# main_board_sch.net
KiCad netlist of a schematic drawn in EAGLE
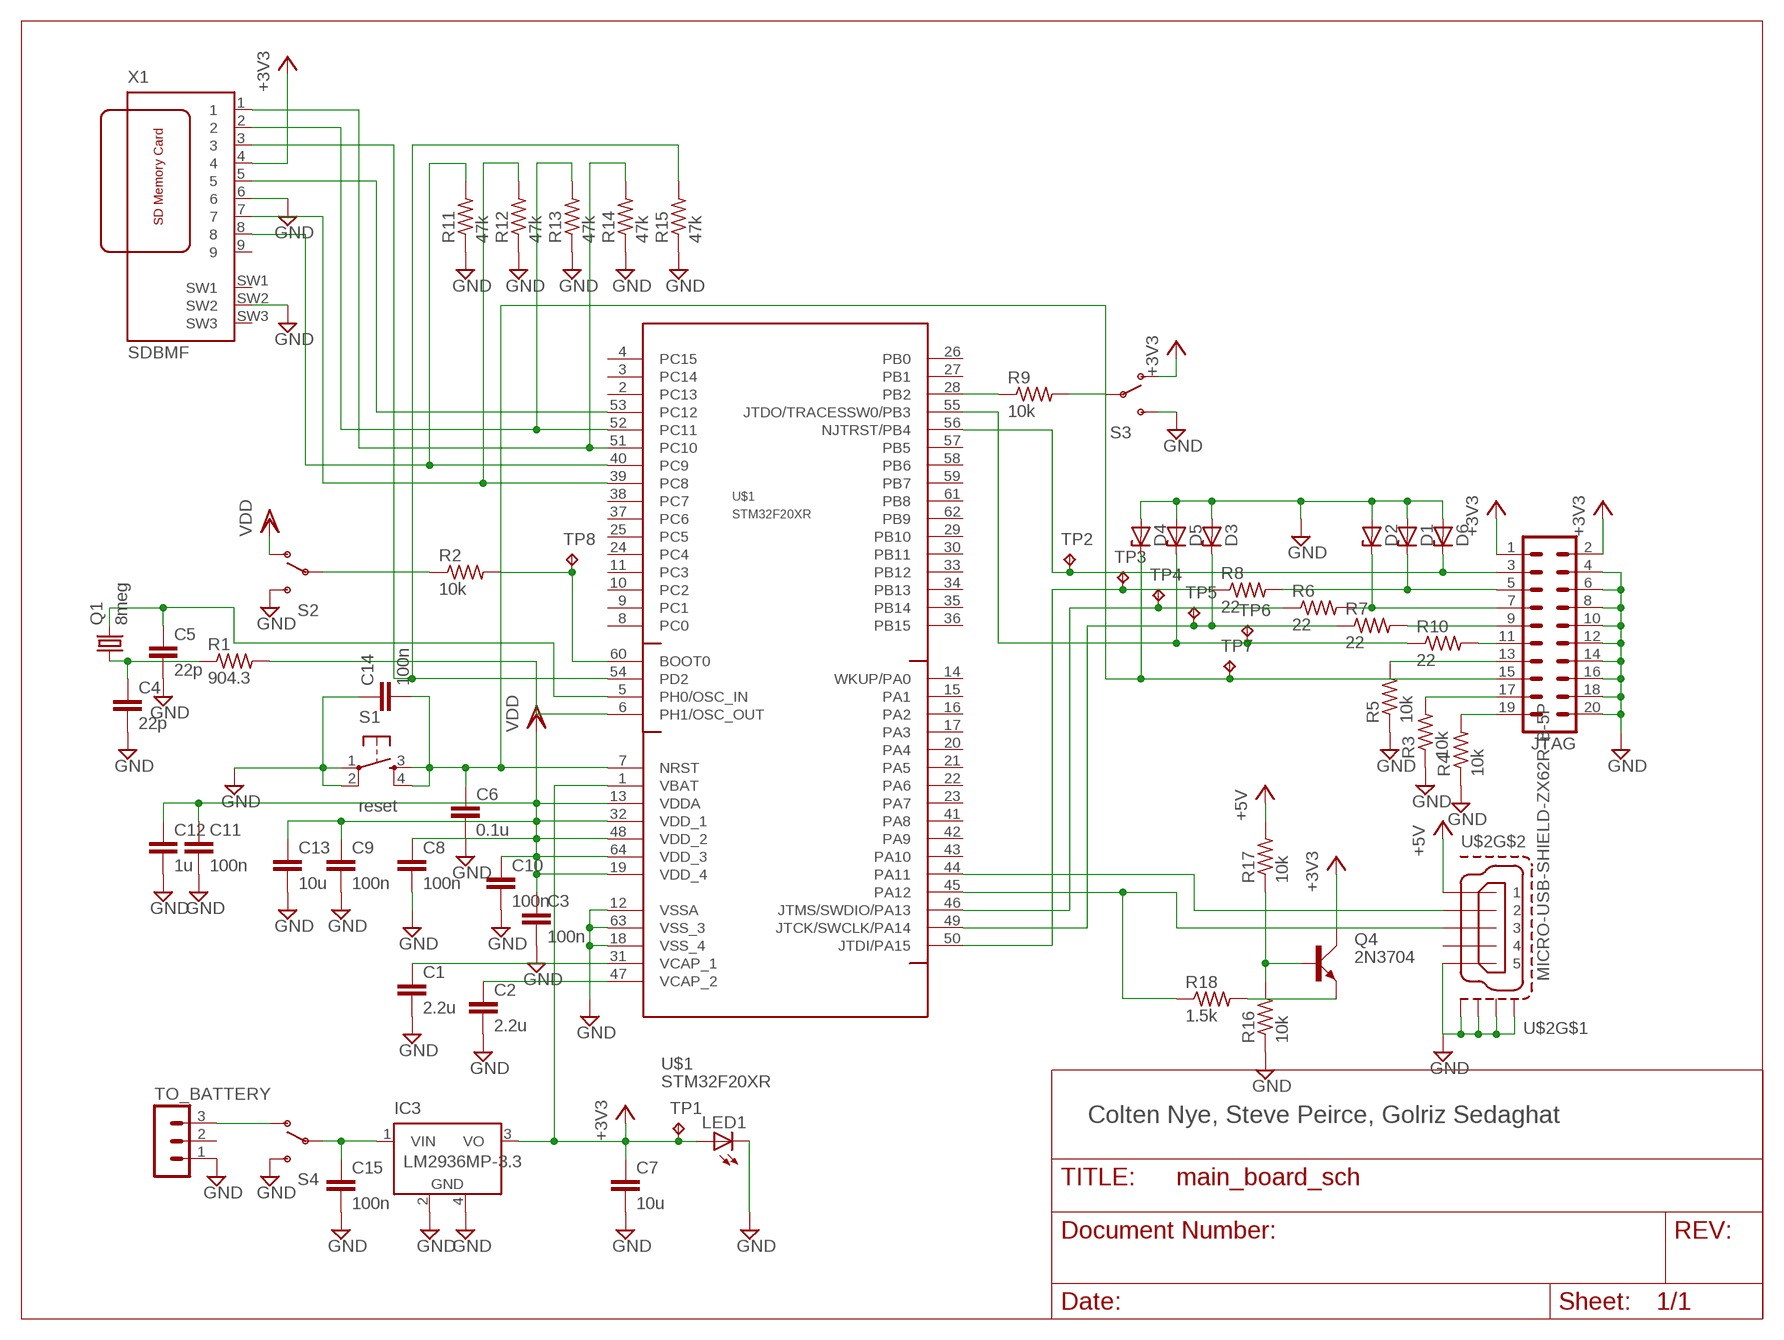
[diagram p0: schematic, sheet 1]

(export (version "E")
  (design (tool "Eeschema 10.0.6"))
  (components
    (comp (ref "C1")
      (value "2.2u")
      (footprint "eagle-import:C0805")
      (libsource (lib "eagle-import") (part "C-EUC0805"))
    )
    (comp (ref "C2")
      (value "2.2u")
      (footprint "eagle-import:C0805")
      (libsource (lib "eagle-import") (part "C-EUC0805"))
    )
    (comp (ref "C3")
      (value "100n")
      (footprint "eagle-import:C0805")
      (libsource (lib "eagle-import") (part "C-EUC0805"))
    )
    (comp (ref "C4")
      (value "22p")
      (footprint "eagle-import:C0805")
      (libsource (lib "eagle-import") (part "C-EUC0805"))
    )
    (comp (ref "C5")
      (value "22p")
      (footprint "eagle-import:C0805")
      (libsource (lib "eagle-import") (part "C-EUC0805"))
    )
    (comp (ref "C6")
      (value "0.1u")
      (footprint "eagle-import:C0805")
      (libsource (lib "eagle-import") (part "C-EUC0805"))
    )
    (comp (ref "C7")
      (value "10u")
      (footprint "eagle-import:C0805")
      (libsource (lib "eagle-import") (part "C-EUC0805"))
    )
    (comp (ref "C8")
      (value "100n")
      (footprint "eagle-import:C0805")
      (libsource (lib "eagle-import") (part "C-EUC0805"))
    )
    (comp (ref "C9")
      (value "100n")
      (footprint "eagle-import:C0805")
      (libsource (lib "eagle-import") (part "C-EUC0805"))
    )
    (comp (ref "C10")
      (value "100n")
      (footprint "eagle-import:C0805")
      (libsource (lib "eagle-import") (part "C-EUC0805"))
    )
    (comp (ref "C11")
      (value "100n")
      (footprint "eagle-import:C0805")
      (libsource (lib "eagle-import") (part "C-EUC0805"))
    )
    (comp (ref "C12")
      (value "1u")
      (footprint "eagle-import:C0805")
      (libsource (lib "eagle-import") (part "C-EUC0805"))
    )
    (comp (ref "C13")
      (value "10u")
      (footprint "eagle-import:C0805")
      (libsource (lib "eagle-import") (part "C-EUC0805"))
    )
    (comp (ref "C14")
      (value "100n")
      (footprint "eagle-import:C0805")
      (libsource (lib "eagle-import") (part "C-EUC0805"))
    )
    (comp (ref "C15")
      (value "100n")
      (footprint "eagle-import:C0805")
      (libsource (lib "eagle-import") (part "C-EUC0805"))
    )
    (comp (ref "D1")
      (value "ZENER-DIODEZD-5")
      (footprint "eagle-import:ZDIO-5")
      (libsource (lib "eagle-import") (part "ZENER-DIODEZD-5"))
    )
    (comp (ref "D2")
      (value "ZENER-DIODEZD-5")
      (footprint "eagle-import:ZDIO-5")
      (libsource (lib "eagle-import") (part "ZENER-DIODEZD-5"))
    )
    (comp (ref "D3")
      (value "ZENER-DIODEZD-5")
      (footprint "eagle-import:ZDIO-5")
      (libsource (lib "eagle-import") (part "ZENER-DIODEZD-5"))
    )
    (comp (ref "D4")
      (value "ZENER-DIODEZD-5")
      (footprint "eagle-import:ZDIO-5")
      (libsource (lib "eagle-import") (part "ZENER-DIODEZD-5"))
    )
    (comp (ref "D5")
      (value "ZENER-DIODEZD-5")
      (footprint "eagle-import:ZDIO-5")
      (libsource (lib "eagle-import") (part "ZENER-DIODEZD-5"))
    )
    (comp (ref "D6")
      (value "ZENER-DIODEZD-5")
      (footprint "eagle-import:ZDIO-5")
      (libsource (lib "eagle-import") (part "ZENER-DIODEZD-5"))
    )
    (comp (ref "IC3")
      (value "LM2936MP-3.3")
      (footprint "eagle-import:SOT223")
      (fields (field (name "MF") "NATIONAL SEMICONDUCTOR") (field (name "MPN") "LM2936MP-3.3/NOPB"))
      (libsource (lib "eagle-import") (part "LM2936MP?-3.3"))
    )
    (comp (ref "JTAG")
      (value "MA10-2")
      (footprint "eagle-import:MA10-2")
      (libsource (lib "eagle-import") (part "MA10-2"))
    )
    (comp (ref "LED1")
      (value "LEDSML0805")
      (footprint "eagle-import:SML0805")
      (libsource (lib "eagle-import") (part "LEDSML0805"))
    )
    (comp (ref "Q1")
      (value "8meg")
      (footprint "eagle-import:HC49_S")
      (libsource (lib "eagle-import") (part "CRYSTALHC49S"))
    )
    (comp (ref "Q4")
      (value "2N3704")
      (footprint "eagle-import:TO92C")
      (libsource (lib "eagle-import") (part "2N3704"))
    )
    (comp (ref "R1")
      (value "904.3")
      (footprint "eagle-import:R0805")
      (libsource (lib "eagle-import") (part "R-US_R0805"))
    )
    (comp (ref "R2")
      (value "10k")
      (footprint "eagle-import:R0805")
      (libsource (lib "eagle-import") (part "R-US_R0805"))
    )
    (comp (ref "R3")
      (value "10k")
      (footprint "eagle-import:R0805")
      (libsource (lib "eagle-import") (part "R-US_R0805"))
    )
    (comp (ref "R4")
      (value "10k")
      (footprint "eagle-import:R0805")
      (libsource (lib "eagle-import") (part "R-US_R0805"))
    )
    (comp (ref "R5")
      (value "10k")
      (footprint "eagle-import:R0805")
      (libsource (lib "eagle-import") (part "R-US_R0805"))
    )
    (comp (ref "R6")
      (value "22")
      (footprint "eagle-import:R0805")
      (libsource (lib "eagle-import") (part "R-US_R0805"))
    )
    (comp (ref "R7")
      (value "22")
      (footprint "eagle-import:R0805")
      (libsource (lib "eagle-import") (part "R-US_R0805"))
    )
    (comp (ref "R8")
      (value "22")
      (footprint "eagle-import:R0805")
      (libsource (lib "eagle-import") (part "R-US_R0805"))
    )
    (comp (ref "R9")
      (value "10k")
      (footprint "eagle-import:R0805")
      (libsource (lib "eagle-import") (part "R-US_R0805"))
    )
    (comp (ref "R10")
      (value "22")
      (footprint "eagle-import:R0805")
      (libsource (lib "eagle-import") (part "R-US_R0805"))
    )
    (comp (ref "R11")
      (value "47k")
      (footprint "eagle-import:R0805")
      (libsource (lib "eagle-import") (part "R-US_R0805"))
    )
    (comp (ref "R12")
      (value "47k")
      (footprint "eagle-import:R0805")
      (libsource (lib "eagle-import") (part "R-US_R0805"))
    )
    (comp (ref "R13")
      (value "47k")
      (footprint "eagle-import:R0805")
      (libsource (lib "eagle-import") (part "R-US_R0805"))
    )
    (comp (ref "R14")
      (value "47k")
      (footprint "eagle-import:R0805")
      (libsource (lib "eagle-import") (part "R-US_R0805"))
    )
    (comp (ref "R15")
      (value "47k")
      (footprint "eagle-import:R0805")
      (libsource (lib "eagle-import") (part "R-US_R0805"))
    )
    (comp (ref "R16")
      (value "10k")
      (footprint "eagle-import:R0805")
      (libsource (lib "eagle-import") (part "R-US_R0805"))
    )
    (comp (ref "R17")
      (value "10k")
      (footprint "eagle-import:R0805")
      (libsource (lib "eagle-import") (part "R-US_R0805"))
    )
    (comp (ref "R18")
      (value "1.5k")
      (footprint "eagle-import:R0805")
      (libsource (lib "eagle-import") (part "R-US_R0805"))
    )
    (comp (ref "S1")
      (value "reset")
      (footprint "eagle-import:TACTILE-SWITCH-SMD")
      (libsource (lib "eagle-import") (part "TAC_SWITCHSMD"))
    )
    (comp (ref "S2")
      (value "SWITCH-SPDT-SMD-A")
      (footprint "eagle-import:SWITCH-SPST-SMD-A")
      (libsource (lib "eagle-import") (part "SWITCH-SPDT-SMD-A"))
    )
    (comp (ref "S3")
      (value "SWITCH-SPDT-SMD-A")
      (footprint "eagle-import:SWITCH-SPST-SMD-A")
      (libsource (lib "eagle-import") (part "SWITCH-SPDT-SMD-A"))
    )
    (comp (ref "S4")
      (value "SWITCH-SPDT-SMD-A")
      (footprint "eagle-import:SWITCH-SPST-SMD-A")
      (libsource (lib "eagle-import") (part "SWITCH-SPDT-SMD-A"))
    )
    (comp (ref "TO_BATTERY")
      (value "MA03-1")
      (footprint "eagle-import:MA03-1")
      (libsource (lib "eagle-import") (part "MA03-1"))
    )
    (comp (ref "TP1")
      (value "TPB1,27")
      (footprint "eagle-import:B1,27")
      (libsource (lib "eagle-import") (part "TPB1,27"))
    )
    (comp (ref "TP2")
      (value "TPB1,27")
      (footprint "eagle-import:B1,27")
      (libsource (lib "eagle-import") (part "TPB1,27"))
    )
    (comp (ref "TP3")
      (value "TPB1,27")
      (footprint "eagle-import:B1,27")
      (libsource (lib "eagle-import") (part "TPB1,27"))
    )
    (comp (ref "TP4")
      (value "TPB1,27")
      (footprint "eagle-import:B1,27")
      (libsource (lib "eagle-import") (part "TPB1,27"))
    )
    (comp (ref "TP5")
      (value "TPB1,27")
      (footprint "eagle-import:B1,27")
      (libsource (lib "eagle-import") (part "TPB1,27"))
    )
    (comp (ref "TP6")
      (value "TPB1,27")
      (footprint "eagle-import:B1,27")
      (libsource (lib "eagle-import") (part "TPB1,27"))
    )
    (comp (ref "TP7")
      (value "TPB1,27")
      (footprint "eagle-import:B1,27")
      (libsource (lib "eagle-import") (part "TPB1,27"))
    )
    (comp (ref "TP8")
      (value "TPB1,27")
      (footprint "eagle-import:B1,27")
      (libsource (lib "eagle-import") (part "TPB1,27"))
    )
    (comp (ref "U$1")
      (value "STM32F20XR")
      (footprint "eagle-import:LQFP64")
      (libsource (lib "eagle-import") (part "STM32F20XR"))
    )
    (comp (ref "U$2")
      (value "MICRO-USB-SHIELD-ZX62R-B-5P")
      (footprint "eagle-import:ZX62R-B-5P")
      (libsource (lib "eagle-import") (part "MICRO-USB-SHIELD-ZX62R-B-5P"))
    )
    (comp (ref "X1")
      (value "SDBMF")
      (footprint "eagle-import:SDBMF-009XXBXX2")
      (libsource (lib "eagle-import") (part "SDBMF"))
    )
  )
  (nets
    (net (code "1") (name "+3V3") (class "Default")
      (node (ref "C7") (pin "1") (pinfunction "1_1") (pintype "passive"))
      (node (ref "IC3") (pin "3") (pinfunction "VO_3") (pintype "passive"))
      (node (ref "JTAG") (pin "1") (pinfunction "1_1") (pintype "passive"))
      (node (ref "JTAG") (pin "2") (pinfunction "2_2") (pintype "passive"))
      (node (ref "LED1") (pin "A") (pinfunction "A_A") (pintype "passive"))
      (node (ref "Q4") (pin "C") (pinfunction "C_C") (pintype "passive"))
      (node (ref "S3") (pin "1") (pinfunction "O_1") (pintype "passive"))
      (node (ref "TP1") (pin "TP") (pinfunction "TP_TP") (pintype "input"))
      (node (ref "U$1") (pin "1") (pinfunction "VBAT_1") (pintype "power_in"))
      (node (ref "X1") (pin "4") (pinfunction "4_4") (pintype "passive"))
    )
    (net (code "2") (name "+5V") (class "Default")
      (node (ref "R17") (pin "2") (pinfunction "2_2") (pintype "passive"))
      (node (ref "U$2") (pin "1") (pinfunction "1_1") (pintype "input"))
    )
    (net (code "3") (name "GND") (class "Default")
      (node (ref "C1") (pin "2") (pinfunction "2_2") (pintype "passive"))
      (node (ref "C10") (pin "2") (pinfunction "2_2") (pintype "passive"))
      (node (ref "C11") (pin "2") (pinfunction "2_2") (pintype "passive"))
      (node (ref "C12") (pin "2") (pinfunction "2_2") (pintype "passive"))
      (node (ref "C13") (pin "2") (pinfunction "2_2") (pintype "passive"))
      (node (ref "C14") (pin "1") (pinfunction "1_1") (pintype "passive"))
      (node (ref "C15") (pin "2") (pinfunction "2_2") (pintype "passive"))
      (node (ref "C2") (pin "2") (pinfunction "2_2") (pintype "passive"))
      (node (ref "C3") (pin "2") (pinfunction "2_2") (pintype "passive"))
      (node (ref "C4") (pin "2") (pinfunction "2_2") (pintype "passive"))
      (node (ref "C5") (pin "2") (pinfunction "2_2") (pintype "passive"))
      (node (ref "C6") (pin "2") (pinfunction "2_2") (pintype "passive"))
      (node (ref "C7") (pin "2") (pinfunction "2_2") (pintype "passive"))
      (node (ref "C8") (pin "2") (pinfunction "2_2") (pintype "passive"))
      (node (ref "C9") (pin "2") (pinfunction "2_2") (pintype "passive"))
      (node (ref "D1") (pin "A") (pinfunction "A_A") (pintype "passive"))
      (node (ref "D2") (pin "A") (pinfunction "A_A") (pintype "passive"))
      (node (ref "D3") (pin "A") (pinfunction "A_A") (pintype "passive"))
      (node (ref "D4") (pin "A") (pinfunction "A_A") (pintype "passive"))
      (node (ref "D5") (pin "A") (pinfunction "A_A") (pintype "passive"))
      (node (ref "D6") (pin "A") (pinfunction "A_A") (pintype "passive"))
      (node (ref "IC3") (pin "2") (pinfunction "GND_2") (pintype "passive"))
      (node (ref "IC3") (pin "4") (pinfunction "GND_4") (pintype "passive"))
      (node (ref "JTAG") (pin "10") (pinfunction "10_10") (pintype "passive"))
      (node (ref "JTAG") (pin "12") (pinfunction "12_12") (pintype "passive"))
      (node (ref "JTAG") (pin "14") (pinfunction "14_14") (pintype "passive"))
      (node (ref "JTAG") (pin "16") (pinfunction "16_16") (pintype "passive"))
      (node (ref "JTAG") (pin "18") (pinfunction "18_18") (pintype "passive"))
      (node (ref "JTAG") (pin "20") (pinfunction "20_20") (pintype "passive"))
      (node (ref "JTAG") (pin "4") (pinfunction "4_4") (pintype "passive"))
      (node (ref "JTAG") (pin "6") (pinfunction "6_6") (pintype "passive"))
      (node (ref "JTAG") (pin "8") (pinfunction "8_8") (pintype "passive"))
      (node (ref "LED1") (pin "C") (pinfunction "C_C") (pintype "passive"))
      (node (ref "R11") (pin "1") (pinfunction "1_1") (pintype "passive"))
      (node (ref "R12") (pin "1") (pinfunction "1_1") (pintype "passive"))
      (node (ref "R13") (pin "1") (pinfunction "1_1") (pintype "passive"))
      (node (ref "R14") (pin "1") (pinfunction "1_1") (pintype "passive"))
      (node (ref "R15") (pin "1") (pinfunction "1_1") (pintype "passive"))
      (node (ref "R16") (pin "1") (pinfunction "1_1") (pintype "passive"))
      (node (ref "R3") (pin "1") (pinfunction "1_1") (pintype "passive"))
      (node (ref "R4") (pin "1") (pinfunction "1_1") (pintype "passive"))
      (node (ref "R5") (pin "1") (pinfunction "1_1") (pintype "passive"))
      (node (ref "S1") (pin "1") (pinfunction "1_1") (pintype "passive"))
      (node (ref "S1") (pin "2") (pinfunction "2_2") (pintype "passive"))
      (node (ref "S2") (pin "3") (pinfunction "S_3") (pintype "passive"))
      (node (ref "S3") (pin "3") (pinfunction "S_3") (pintype "passive"))
      (node (ref "S4") (pin "3") (pinfunction "S_3") (pintype "passive"))
      (node (ref "TO_BATTERY") (pin "1") (pinfunction "1_1") (pintype "passive"))
      (node (ref "U$1") (pin "12") (pinfunction "VSSA_12") (pintype "power_in"))
      (node (ref "U$1") (pin "18") (pinfunction "VSS_4_18") (pintype "power_in"))
      (node (ref "U$1") (pin "63") (pinfunction "VSS_3_63") (pintype "power_in"))
      (node (ref "U$2") (pin "5") (pinfunction "5_5") (pintype "input"))
      (node (ref "U$2") (pin "M1") (pinfunction "S1_M1") (pintype "passive"))
      (node (ref "U$2") (pin "M2") (pinfunction "S2_M2") (pintype "passive"))
      (node (ref "U$2") (pin "M3") (pinfunction "S3_M3") (pintype "passive"))
      (node (ref "U$2") (pin "M4") (pinfunction "S4_M4") (pintype "passive"))
      (node (ref "X1") (pin "6") (pinfunction "6_6") (pintype "passive"))
      (node (ref "X1") (pin "SW2") (pinfunction "SW2_SW2") (pintype "passive"))
    )
    (net (code "4") (name "Net-(C4-Pad1)") (class "Default")
      (node (ref "C4") (pin "1") (pinfunction "1_1") (pintype "passive"))
      (node (ref "Q1") (pin "1") (pinfunction "1_1") (pintype "passive"))
      (node (ref "R1") (pin "1") (pinfunction "1_1") (pintype "passive"))
    )
    (net (code "5") (name "Net-(D1-PadC)") (class "Default")
      (node (ref "D1") (pin "C") (pinfunction "C_C") (pintype "passive"))
      (node (ref "JTAG") (pin "5") (pinfunction "5_5") (pintype "passive"))
      (node (ref "R8") (pin "2") (pinfunction "2_2") (pintype "passive"))
    )
    (net (code "6") (name "Net-(D2-PadC)") (class "Default")
      (node (ref "D2") (pin "C") (pinfunction "C_C") (pintype "passive"))
      (node (ref "JTAG") (pin "7") (pinfunction "7_7") (pintype "passive"))
      (node (ref "R6") (pin "2") (pinfunction "2_2") (pintype "passive"))
    )
    (net (code "7") (name "Net-(IC3-VIN)") (class "Default")
      (node (ref "C15") (pin "1") (pinfunction "1_1") (pintype "passive"))
      (node (ref "IC3") (pin "1") (pinfunction "VIN_1") (pintype "input"))
      (node (ref "S4") (pin "2") (pinfunction "P_2") (pintype "passive"))
    )
    (net (code "8") (name "Net-(JTAG-Pad9)") (class "Default")
      (node (ref "JTAG") (pin "9") (pinfunction "9_9") (pintype "passive"))
      (node (ref "R7") (pin "2") (pinfunction "2_2") (pintype "passive"))
    )
    (net (code "9") (name "Net-(JTAG-Pad11)") (class "Default")
      (node (ref "JTAG") (pin "11") (pinfunction "11_11") (pintype "passive"))
      (node (ref "R10") (pin "2") (pinfunction "2_2") (pintype "passive"))
    )
    (net (code "10") (name "Net-(JTAG-Pad13)") (class "Default")
      (node (ref "JTAG") (pin "13") (pinfunction "13_13") (pintype "passive"))
      (node (ref "R5") (pin "2") (pinfunction "2_2") (pintype "passive"))
    )
    (net (code "11") (name "Net-(JTAG-Pad17)") (class "Default")
      (node (ref "JTAG") (pin "17") (pinfunction "17_17") (pintype "passive"))
      (node (ref "R3") (pin "2") (pinfunction "2_2") (pintype "passive"))
    )
    (net (code "12") (name "Net-(JTAG-Pad19)") (class "Default")
      (node (ref "JTAG") (pin "19") (pinfunction "19_19") (pintype "passive"))
      (node (ref "R4") (pin "2") (pinfunction "2_2") (pintype "passive"))
    )
    (net (code "13") (name "Net-(Q4-PadB)") (class "Default")
      (node (ref "Q4") (pin "B") (pinfunction "B_B") (pintype "passive"))
      (node (ref "R16") (pin "2") (pinfunction "2_2") (pintype "passive"))
      (node (ref "R17") (pin "1") (pinfunction "1_1") (pintype "passive"))
    )
    (net (code "14") (name "Net-(Q4-PadE)") (class "Default")
      (node (ref "Q4") (pin "E") (pinfunction "E_E") (pintype "passive"))
      (node (ref "R18") (pin "2") (pinfunction "2_2") (pintype "passive"))
    )
    (net (code "15") (name "Net-(S2-P)") (class "Default")
      (node (ref "R2") (pin "1") (pinfunction "1_1") (pintype "passive"))
      (node (ref "S2") (pin "2") (pinfunction "P_2") (pintype "passive"))
    )
    (net (code "16") (name "Net-(S3-P)") (class "Default")
      (node (ref "R9") (pin "2") (pinfunction "2_2") (pintype "passive"))
      (node (ref "S3") (pin "2") (pinfunction "P_2") (pintype "passive"))
    )
    (net (code "17") (name "Net-(S4-O)") (class "Default")
      (node (ref "S4") (pin "1") (pinfunction "O_1") (pintype "passive"))
      (node (ref "TO_BATTERY") (pin "3") (pinfunction "3_3") (pintype "passive"))
    )
    (net (code "18") (name "Net-(U$1-BOOT0)") (class "Default")
      (node (ref "R2") (pin "2") (pinfunction "2_2") (pintype "passive"))
      (node (ref "TP8") (pin "TP") (pinfunction "TP_TP") (pintype "input"))
      (node (ref "U$1") (pin "60") (pinfunction "BOOT0_60") (pintype "bidirectional"))
    )
    (net (code "19") (name "Net-(U$1-JTCK{slash}SWCLK{slash}PA14)") (class "Default")
      (node (ref "D3") (pin "C") (pinfunction "C_C") (pintype "passive"))
      (node (ref "R7") (pin "1") (pinfunction "1_1") (pintype "passive"))
      (node (ref "TP5") (pin "TP") (pinfunction "TP_TP") (pintype "input"))
      (node (ref "U$1") (pin "49") (pinfunction "JTCK/SWCLK/PA14_49") (pintype "bidirectional"))
    )
    (net (code "20") (name "Net-(U$1-JTDI{slash}PA15)") (class "Default")
      (node (ref "R8") (pin "1") (pinfunction "1_1") (pintype "passive"))
      (node (ref "TP3") (pin "TP") (pinfunction "TP_TP") (pintype "input"))
      (node (ref "U$1") (pin "50") (pinfunction "JTDI/PA15_50") (pintype "bidirectional"))
    )
    (net (code "21") (name "Net-(U$1-JTDO{slash}TRACESSW0{slash}PB3)") (class "Default")
      (node (ref "D5") (pin "C") (pinfunction "C_C") (pintype "passive"))
      (node (ref "R10") (pin "1") (pinfunction "1_1") (pintype "passive"))
      (node (ref "TP6") (pin "TP") (pinfunction "TP_TP") (pintype "input"))
      (node (ref "U$1") (pin "55") (pinfunction "JTDO/TRACESSW0/PB3_55") (pintype "bidirectional"))
    )
    (net (code "22") (name "Net-(U$1-JTMS{slash}SWDIO{slash}PA13)") (class "Default")
      (node (ref "R6") (pin "1") (pinfunction "1_1") (pintype "passive"))
      (node (ref "TP4") (pin "TP") (pinfunction "TP_TP") (pintype "input"))
      (node (ref "U$1") (pin "46") (pinfunction "JTMS/SWDIO/PA13_46") (pintype "bidirectional"))
    )
    (net (code "23") (name "Net-(U$1-NJTRST{slash}PB4)") (class "Default")
      (node (ref "D6") (pin "C") (pinfunction "C_C") (pintype "passive"))
      (node (ref "JTAG") (pin "3") (pinfunction "3_3") (pintype "passive"))
      (node (ref "TP2") (pin "TP") (pinfunction "TP_TP") (pintype "input"))
      (node (ref "U$1") (pin "56") (pinfunction "NJTRST/PB4_56") (pintype "bidirectional"))
    )
    (net (code "24") (name "Net-(U$1-NRST)") (class "Default")
      (node (ref "C14") (pin "2") (pinfunction "2_2") (pintype "passive"))
      (node (ref "C6") (pin "1") (pinfunction "1_1") (pintype "passive"))
      (node (ref "D4") (pin "C") (pinfunction "C_C") (pintype "passive"))
      (node (ref "JTAG") (pin "15") (pinfunction "15_15") (pintype "passive"))
      (node (ref "S1") (pin "3") (pinfunction "3_3") (pintype "passive"))
      (node (ref "S1") (pin "4") (pinfunction "4_4") (pintype "passive"))
      (node (ref "TP7") (pin "TP") (pinfunction "TP_TP") (pintype "input"))
      (node (ref "U$1") (pin "7") (pinfunction "NRST_7") (pintype "power_in"))
    )
    (net (code "25") (name "Net-(U$1-PA11)") (class "Default")
      (node (ref "U$1") (pin "44") (pinfunction "PA11_44") (pintype "bidirectional"))
      (node (ref "U$2") (pin "2") (pinfunction "2_2") (pintype "input"))
    )
    (net (code "26") (name "Net-(U$1-PA12)") (class "Default")
      (node (ref "R18") (pin "1") (pinfunction "1_1") (pintype "passive"))
      (node (ref "U$1") (pin "45") (pinfunction "PA12_45") (pintype "bidirectional"))
      (node (ref "U$2") (pin "3") (pinfunction "3_3") (pintype "input"))
    )
    (net (code "27") (name "Net-(U$1-PB2)") (class "Default")
      (node (ref "R9") (pin "1") (pinfunction "1_1") (pintype "passive"))
      (node (ref "U$1") (pin "28") (pinfunction "PB2_28") (pintype "bidirectional"))
    )
    (net (code "28") (name "Net-(U$1-PC8)") (class "Default")
      (node (ref "R12") (pin "2") (pinfunction "2_2") (pintype "passive"))
      (node (ref "U$1") (pin "39") (pinfunction "PC8_39") (pintype "bidirectional"))
      (node (ref "X1") (pin "7") (pinfunction "7_7") (pintype "passive"))
    )
    (net (code "29") (name "Net-(U$1-PC9)") (class "Default")
      (node (ref "R11") (pin "2") (pinfunction "2_2") (pintype "passive"))
      (node (ref "U$1") (pin "40") (pinfunction "PC9_40") (pintype "bidirectional"))
      (node (ref "X1") (pin "8") (pinfunction "8_8") (pintype "passive"))
    )
    (net (code "30") (name "Net-(U$1-PC10)") (class "Default")
      (node (ref "R14") (pin "2") (pinfunction "2_2") (pintype "passive"))
      (node (ref "U$1") (pin "51") (pinfunction "PC10_51") (pintype "bidirectional"))
      (node (ref "X1") (pin "1") (pinfunction "1_1") (pintype "passive"))
    )
    (net (code "31") (name "Net-(U$1-PC11)") (class "Default")
      (node (ref "R13") (pin "2") (pinfunction "2_2") (pintype "passive"))
      (node (ref "U$1") (pin "52") (pinfunction "PC11_52") (pintype "bidirectional"))
      (node (ref "X1") (pin "2") (pinfunction "2_2") (pintype "passive"))
    )
    (net (code "32") (name "Net-(U$1-PC12)") (class "Default")
      (node (ref "U$1") (pin "53") (pinfunction "PC12_53") (pintype "bidirectional"))
      (node (ref "X1") (pin "5") (pinfunction "5_5") (pintype "passive"))
    )
    (net (code "33") (name "Net-(U$1-PD2)") (class "Default")
      (node (ref "R15") (pin "2") (pinfunction "2_2") (pintype "passive"))
      (node (ref "U$1") (pin "54") (pinfunction "PD2_54") (pintype "bidirectional"))
      (node (ref "X1") (pin "3") (pinfunction "3_3") (pintype "passive"))
    )
    (net (code "34") (name "Net-(U$1-PH0{slash}OSC_IN)") (class "Default")
      (node (ref "C5") (pin "1") (pinfunction "1_1") (pintype "passive"))
      (node (ref "Q1") (pin "2") (pinfunction "2_2") (pintype "passive"))
      (node (ref "U$1") (pin "5") (pinfunction "PH0/OSC_IN_5") (pintype "bidirectional"))
    )
    (net (code "35") (name "Net-(U$1-PH1{slash}OSC_OUT)") (class "Default")
      (node (ref "R1") (pin "2") (pinfunction "2_2") (pintype "passive"))
      (node (ref "U$1") (pin "6") (pinfunction "PH1/OSC_OUT_6") (pintype "bidirectional"))
    )
    (net (code "36") (name "Net-(U$1-VCAP_1)") (class "Default")
      (node (ref "C1") (pin "1") (pinfunction "1_1") (pintype "passive"))
      (node (ref "U$1") (pin "31") (pinfunction "VCAP_1_31") (pintype "power_in"))
    )
    (net (code "37") (name "Net-(U$1-VCAP_2)") (class "Default")
      (node (ref "C2") (pin "1") (pinfunction "1_1") (pintype "passive"))
      (node (ref "U$1") (pin "47") (pinfunction "VCAP_2_47") (pintype "power_in"))
    )
    (net (code "38") (name "VDD") (class "Default")
      (node (ref "C10") (pin "1") (pinfunction "1_1") (pintype "passive"))
      (node (ref "C11") (pin "1") (pinfunction "1_1") (pintype "passive"))
      (node (ref "C12") (pin "1") (pinfunction "1_1") (pintype "passive"))
      (node (ref "C13") (pin "1") (pinfunction "1_1") (pintype "passive"))
      (node (ref "C3") (pin "1") (pinfunction "1_1") (pintype "passive"))
      (node (ref "C8") (pin "1") (pinfunction "1_1") (pintype "passive"))
      (node (ref "C9") (pin "1") (pinfunction "1_1") (pintype "passive"))
      (node (ref "S2") (pin "1") (pinfunction "O_1") (pintype "passive"))
      (node (ref "U$1") (pin "13") (pinfunction "VDDA_13") (pintype "power_in"))
      (node (ref "U$1") (pin "19") (pinfunction "VDD_4_19") (pintype "power_in"))
      (node (ref "U$1") (pin "32") (pinfunction "VDD_1_32") (pintype "power_in"))
      (node (ref "U$1") (pin "48") (pinfunction "VDD_2_48") (pintype "power_in"))
      (node (ref "U$1") (pin "64") (pinfunction "VDD_3_64") (pintype "power_in"))
    )
    (net (code "39") (name "unconnected-(TO_BATTERY-Pad2)") (class "Default")
      (node (ref "TO_BATTERY") (pin "2") (pinfunction "2_2") (pintype "passive"))
    )
    (net (code "40") (name "unconnected-(U$1-PA1-Pad15)") (class "Default")
      (node (ref "U$1") (pin "15") (pinfunction "PA1_15") (pintype "bidirectional"))
    )
    (net (code "41") (name "unconnected-(U$1-PA2-Pad16)") (class "Default")
      (node (ref "U$1") (pin "16") (pinfunction "PA2_16") (pintype "bidirectional"))
    )
    (net (code "42") (name "unconnected-(U$1-PA3-Pad17)") (class "Default")
      (node (ref "U$1") (pin "17") (pinfunction "PA3_17") (pintype "bidirectional"))
    )
    (net (code "43") (name "unconnected-(U$1-PA4-Pad20)") (class "Default")
      (node (ref "U$1") (pin "20") (pinfunction "PA4_20") (pintype "bidirectional"))
    )
    (net (code "44") (name "unconnected-(U$1-PA5-Pad21)") (class "Default")
      (node (ref "U$1") (pin "21") (pinfunction "PA5_21") (pintype "bidirectional"))
    )
    (net (code "45") (name "unconnected-(U$1-PA6-Pad22)") (class "Default")
      (node (ref "U$1") (pin "22") (pinfunction "PA6_22") (pintype "bidirectional"))
    )
    (net (code "46") (name "unconnected-(U$1-PA7-Pad23)") (class "Default")
      (node (ref "U$1") (pin "23") (pinfunction "PA7_23") (pintype "bidirectional"))
    )
    (net (code "47") (name "unconnected-(U$1-PA8-Pad41)") (class "Default")
      (node (ref "U$1") (pin "41") (pinfunction "PA8_41") (pintype "bidirectional"))
    )
    (net (code "48") (name "unconnected-(U$1-PA9-Pad42)") (class "Default")
      (node (ref "U$1") (pin "42") (pinfunction "PA9_42") (pintype "bidirectional"))
    )
    (net (code "49") (name "unconnected-(U$1-PA10-Pad43)") (class "Default")
      (node (ref "U$1") (pin "43") (pinfunction "PA10_43") (pintype "bidirectional"))
    )
    (net (code "50") (name "unconnected-(U$1-PB0-Pad26)") (class "Default")
      (node (ref "U$1") (pin "26") (pinfunction "PB0_26") (pintype "bidirectional"))
    )
    (net (code "51") (name "unconnected-(U$1-PB1-Pad27)") (class "Default")
      (node (ref "U$1") (pin "27") (pinfunction "PB1_27") (pintype "bidirectional"))
    )
    (net (code "52") (name "unconnected-(U$1-PB5-Pad57)") (class "Default")
      (node (ref "U$1") (pin "57") (pinfunction "PB5_57") (pintype "bidirectional"))
    )
    (net (code "53") (name "unconnected-(U$1-PB6-Pad58)") (class "Default")
      (node (ref "U$1") (pin "58") (pinfunction "PB6_58") (pintype "bidirectional"))
    )
    (net (code "54") (name "unconnected-(U$1-PB7-Pad59)") (class "Default")
      (node (ref "U$1") (pin "59") (pinfunction "PB7_59") (pintype "bidirectional"))
    )
    (net (code "55") (name "unconnected-(U$1-PB8-Pad61)") (class "Default")
      (node (ref "U$1") (pin "61") (pinfunction "PB8_61") (pintype "bidirectional"))
    )
    (net (code "56") (name "unconnected-(U$1-PB9-Pad62)") (class "Default")
      (node (ref "U$1") (pin "62") (pinfunction "PB9_62") (pintype "bidirectional"))
    )
    (net (code "57") (name "unconnected-(U$1-PB10-Pad29)") (class "Default")
      (node (ref "U$1") (pin "29") (pinfunction "PB10_29") (pintype "bidirectional"))
    )
    (net (code "58") (name "unconnected-(U$1-PB11-Pad30)") (class "Default")
      (node (ref "U$1") (pin "30") (pinfunction "PB11_30") (pintype "bidirectional"))
    )
    (net (code "59") (name "unconnected-(U$1-PB12-Pad33)") (class "Default")
      (node (ref "U$1") (pin "33") (pinfunction "PB12_33") (pintype "bidirectional"))
    )
    (net (code "60") (name "unconnected-(U$1-PB13-Pad34)") (class "Default")
      (node (ref "U$1") (pin "34") (pinfunction "PB13_34") (pintype "bidirectional"))
    )
    (net (code "61") (name "unconnected-(U$1-PB14-Pad35)") (class "Default")
      (node (ref "U$1") (pin "35") (pinfunction "PB14_35") (pintype "bidirectional"))
    )
    (net (code "62") (name "unconnected-(U$1-PB15-Pad36)") (class "Default")
      (node (ref "U$1") (pin "36") (pinfunction "PB15_36") (pintype "bidirectional"))
    )
    (net (code "63") (name "unconnected-(U$1-PC0-Pad8)") (class "Default")
      (node (ref "U$1") (pin "8") (pinfunction "PC0_8") (pintype "bidirectional"))
    )
    (net (code "64") (name "unconnected-(U$1-PC1-Pad9)") (class "Default")
      (node (ref "U$1") (pin "9") (pinfunction "PC1_9") (pintype "bidirectional"))
    )
    (net (code "65") (name "unconnected-(U$1-PC2-Pad10)") (class "Default")
      (node (ref "U$1") (pin "10") (pinfunction "PC2_10") (pintype "bidirectional"))
    )
    (net (code "66") (name "unconnected-(U$1-PC3-Pad11)") (class "Default")
      (node (ref "U$1") (pin "11") (pinfunction "PC3_11") (pintype "bidirectional"))
    )
    (net (code "67") (name "unconnected-(U$1-PC4-Pad24)") (class "Default")
      (node (ref "U$1") (pin "24") (pinfunction "PC4_24") (pintype "bidirectional"))
    )
    (net (code "68") (name "unconnected-(U$1-PC5-Pad25)") (class "Default")
      (node (ref "U$1") (pin "25") (pinfunction "PC5_25") (pintype "bidirectional"))
    )
    (net (code "69") (name "unconnected-(U$1-PC6-Pad37)") (class "Default")
      (node (ref "U$1") (pin "37") (pinfunction "PC6_37") (pintype "bidirectional"))
    )
    (net (code "70") (name "unconnected-(U$1-PC7-Pad38)") (class "Default")
      (node (ref "U$1") (pin "38") (pinfunction "PC7_38") (pintype "bidirectional"))
    )
    (net (code "71") (name "unconnected-(U$1-PC13-Pad2)") (class "Default")
      (node (ref "U$1") (pin "2") (pinfunction "PC13_2") (pintype "bidirectional"))
    )
    (net (code "72") (name "unconnected-(U$1-PC14-Pad3)") (class "Default")
      (node (ref "U$1") (pin "3") (pinfunction "PC14_3") (pintype "bidirectional"))
    )
    (net (code "73") (name "unconnected-(U$1-PC15-Pad4)") (class "Default")
      (node (ref "U$1") (pin "4") (pinfunction "PC15_4") (pintype "bidirectional"))
    )
    (net (code "74") (name "unconnected-(U$1-WKUP{slash}PA0-Pad14)") (class "Default")
      (node (ref "U$1") (pin "14") (pinfunction "WKUP/PA0_14") (pintype "bidirectional"))
    )
    (net (code "75") (name "unconnected-(U$2-Pad4)") (class "Default")
      (node (ref "U$2") (pin "4") (pinfunction "4_4") (pintype "input"))
    )
    (net (code "76") (name "unconnected-(X1-Pad9)") (class "Default")
      (node (ref "X1") (pin "9") (pinfunction "9_9") (pintype "passive"))
    )
    (net (code "77") (name "unconnected-(X1-PadSW1)") (class "Default")
      (node (ref "X1") (pin "SW1") (pinfunction "SW1_SW1") (pintype "passive"))
    )
    (net (code "78") (name "unconnected-(X1-PadSW3)") (class "Default")
      (node (ref "X1") (pin "SW3") (pinfunction "SW3_SW3") (pintype "passive"))
    )
  )
)
